# INSIDER02.net
KiCad netlist of a schematic drawn in EAGLE
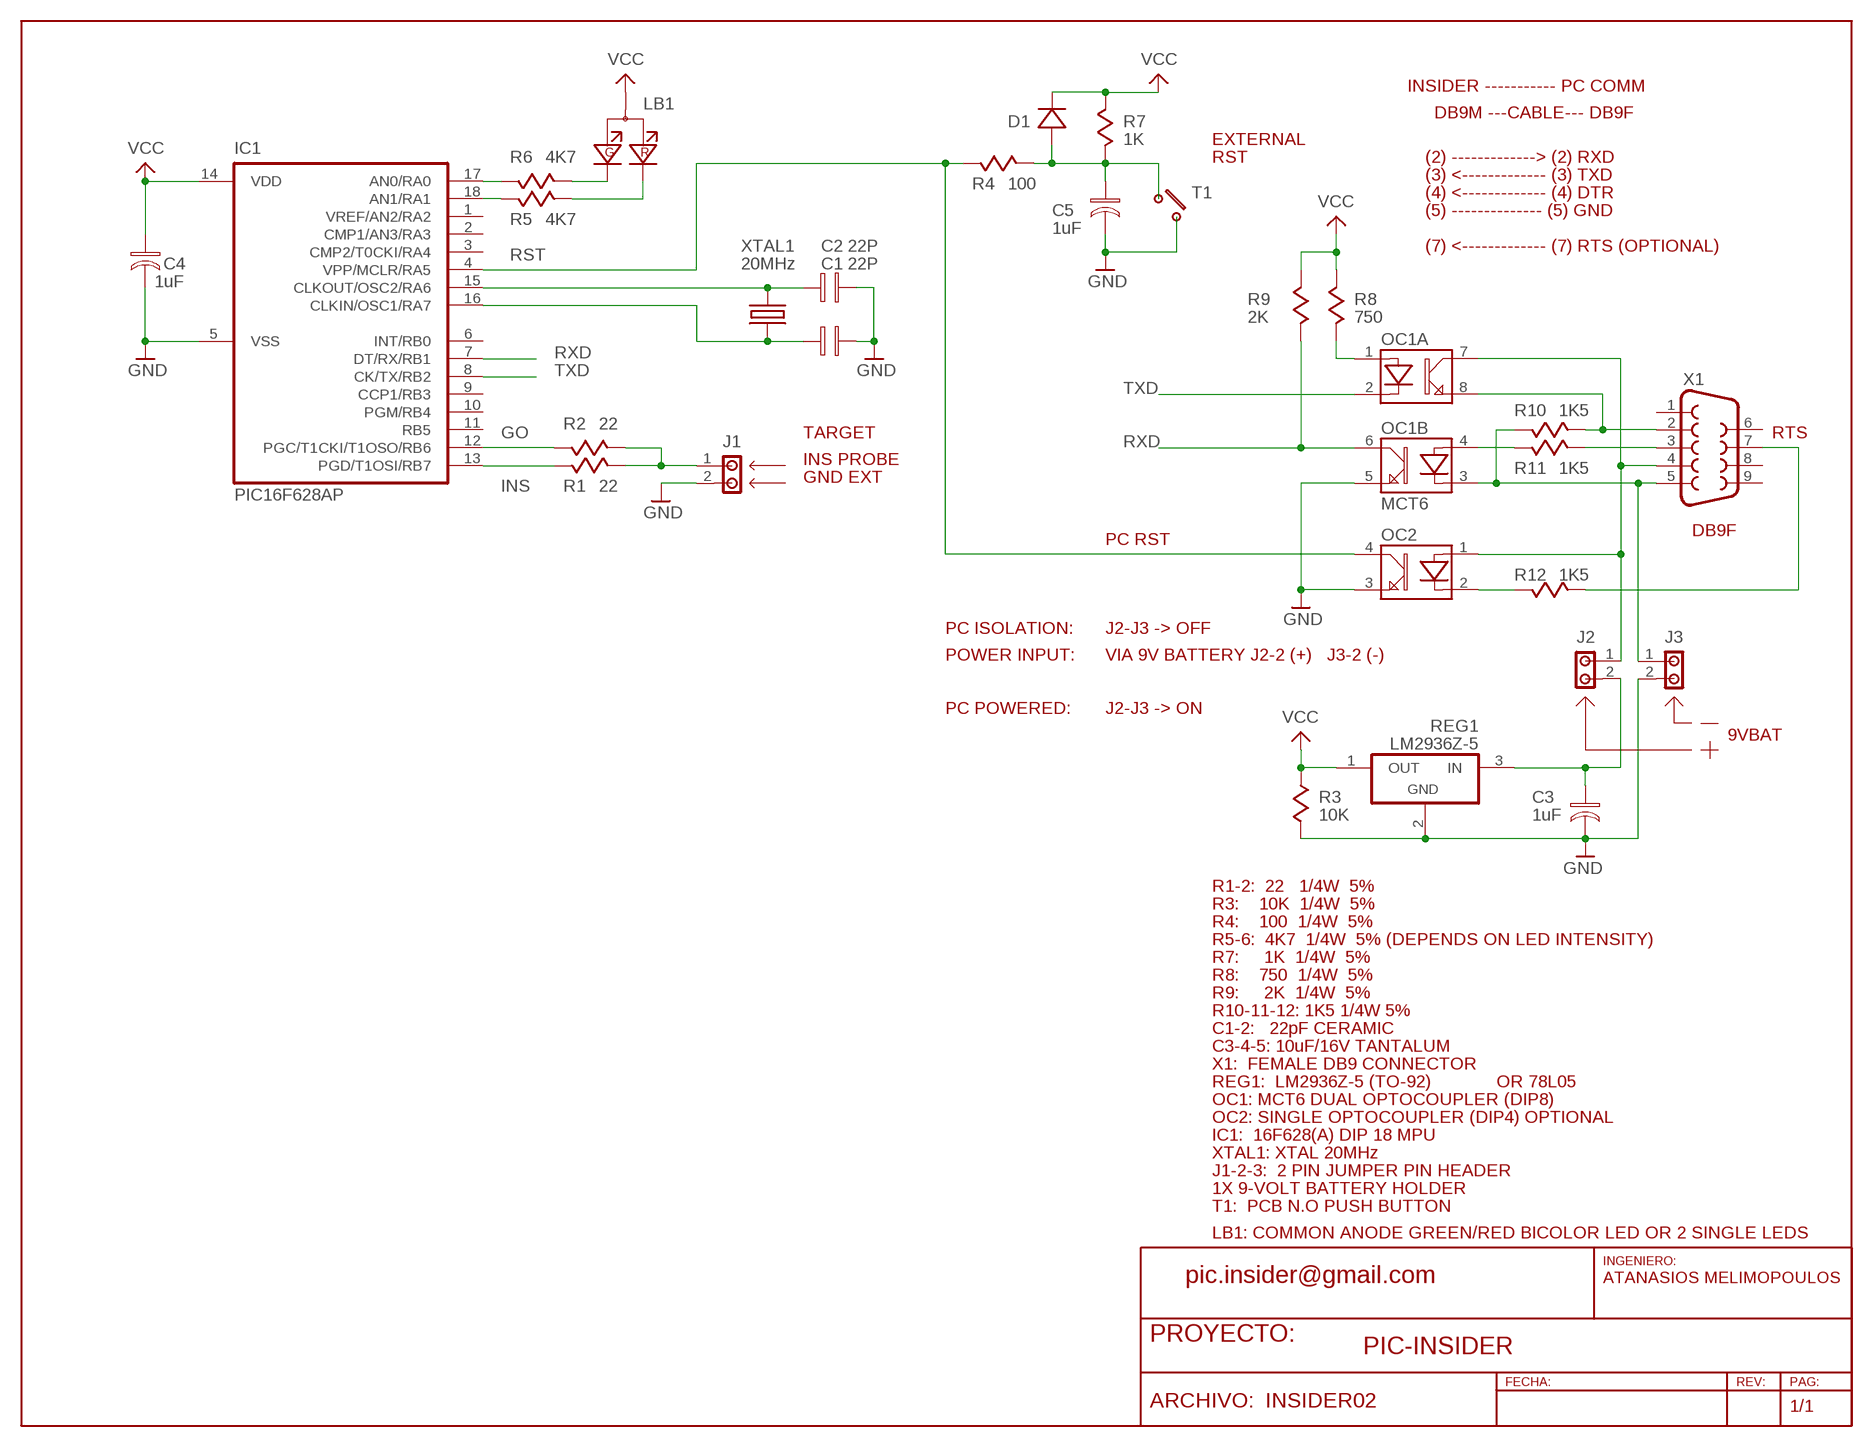
[diagram p0: schematic, sheet 1]

(export (version "E")
  (design (tool "Eeschema 10.0.6"))
  (components
    (comp (ref "C1")
      (value "22P")
      (footprint "eagle-import:C02")
      (libsource (lib "eagle-import") (part "CAP02"))
    )
    (comp (ref "C2")
      (value "22P")
      (footprint "eagle-import:C02")
      (libsource (lib "eagle-import") (part "CAP02"))
    )
    (comp (ref "C3")
      (value "1uF")
      (footprint "eagle-import:CP01")
      (libsource (lib "eagle-import") (part "CAPE01"))
    )
    (comp (ref "C4")
      (value "1uF")
      (footprint "eagle-import:CP01")
      (libsource (lib "eagle-import") (part "CAPE01"))
    )
    (comp (ref "C5")
      (value "1uF")
      (footprint "eagle-import:CP01")
      (libsource (lib "eagle-import") (part "CAPE01"))
    )
    (comp (ref "D1")
      (value "1N4148")
      (footprint "eagle-import:D03")
      (libsource (lib "eagle-import") (part "DIODE03"))
    )
    (comp (ref "IC1")
      (value "PIC16F628AP")
      (footprint "eagle-import:DIL18")
      (libsource (lib "eagle-import") (part "PIC16F6P28A"))
    )
    (comp (ref "J1")
      (value "JMP2")
      (footprint "eagle-import:JP2")
      (libsource (lib "eagle-import") (part "JMP2"))
    )
    (comp (ref "J2")
      (value "JMP2")
      (footprint "eagle-import:JP2")
      (libsource (lib "eagle-import") (part "JMP2"))
    )
    (comp (ref "J3")
      (value "JMP2")
      (footprint "eagle-import:JP2")
      (libsource (lib "eagle-import") (part "JMP2"))
    )
    (comp (ref "LB1")
      (value "LEDBIAC")
      (footprint "eagle-import:LEDBAC")
      (libsource (lib "eagle-import") (part "LEDBIAC"))
    )
    (comp (ref "OC1")
      (value "MCT6")
      (footprint "eagle-import:DIL08")
      (libsource (lib "eagle-import") (part "OPTO2G"))
    )
    (comp (ref "OC2")
      (value "OPTO1A")
      (footprint "eagle-import:DIL04")
      (libsource (lib "eagle-import") (part "OPTO1A"))
    )
    (comp (ref "R1")
      (value "22")
      (footprint "eagle-import:R03")
      (libsource (lib "eagle-import") (part "RES03"))
    )
    (comp (ref "R2")
      (value "22")
      (footprint "eagle-import:R03")
      (libsource (lib "eagle-import") (part "RES03"))
    )
    (comp (ref "R3")
      (value "10K")
      (footprint "eagle-import:R03")
      (libsource (lib "eagle-import") (part "RES03"))
    )
    (comp (ref "R4")
      (value "100")
      (footprint "eagle-import:R03")
      (libsource (lib "eagle-import") (part "RES03"))
    )
    (comp (ref "R5")
      (value "4K7")
      (footprint "eagle-import:R03")
      (libsource (lib "eagle-import") (part "RES03"))
    )
    (comp (ref "R6")
      (value "4K7")
      (footprint "eagle-import:R03")
      (libsource (lib "eagle-import") (part "RES03"))
    )
    (comp (ref "R7")
      (value "1K")
      (footprint "eagle-import:R03")
      (libsource (lib "eagle-import") (part "RES03"))
    )
    (comp (ref "R8")
      (value "750")
      (footprint "eagle-import:R03")
      (libsource (lib "eagle-import") (part "RES03"))
    )
    (comp (ref "R9")
      (value "2K")
      (footprint "eagle-import:R03")
      (libsource (lib "eagle-import") (part "RES03"))
    )
    (comp (ref "R10")
      (value "1K5")
      (footprint "eagle-import:R03")
      (libsource (lib "eagle-import") (part "RES03"))
    )
    (comp (ref "R11")
      (value "1K5")
      (footprint "eagle-import:R03")
      (libsource (lib "eagle-import") (part "RES03"))
    )
    (comp (ref "R12")
      (value "1K5")
      (footprint "eagle-import:R03")
      (libsource (lib "eagle-import") (part "RES03"))
    )
    (comp (ref "REG1")
      (value "LM2936Z-5")
      (footprint "eagle-import:TO92A")
      (libsource (lib "eagle-import") (part "78XXL"))
    )
    (comp (ref "T1")
      (value "TEC3")
      (footprint "eagle-import:TEC3L")
      (libsource (lib "eagle-import") (part "TEC3"))
    )
    (comp (ref "X1")
      (value "F09D")
      (footprint "eagle-import:F09D")
      (libsource (lib "eagle-import") (part "F09D"))
    )
    (comp (ref "XTAL1")
      (value "20MHz")
      (footprint "eagle-import:HC49V")
      (libsource (lib "eagle-import") (part "XTALV300"))
    )
  )
  (nets
    (net (code "1") (name "/GO") (class "Default")
      (node (ref "IC1") (pin "12") (pinfunction "PGC/T1CKI/T1OSO/RB6_12") (pintype "bidirectional"))
      (node (ref "R2") (pin "P$2") (pinfunction "2_P$2") (pintype "passive"))
    )
    (net (code "2") (name "/INS") (class "Default")
      (node (ref "IC1") (pin "13") (pinfunction "PGD/T1OSI/RB7_13") (pintype "bidirectional"))
      (node (ref "R1") (pin "P$1") (pinfunction "1_P$1") (pintype "passive"))
    )
    (net (code "3") (name "/RST") (class "Default")
      (node (ref "IC1") (pin "4") (pinfunction "VPP/MCLR/RA5_4") (pintype "input"))
      (node (ref "OC2") (pin "4") (pinfunction "C_4") (pintype "passive"))
      (node (ref "R4") (pin "P$2") (pinfunction "2_P$2") (pintype "passive"))
    )
    (net (code "4") (name "/RXD") (class "Default")
      (node (ref "IC1") (pin "7") (pinfunction "DT/RX/RB1_7") (pintype "bidirectional"))
      (node (ref "OC1") (pin "6") (pinfunction "C_6") (pintype "passive"))
      (node (ref "R9") (pin "P$2") (pinfunction "2_P$2") (pintype "passive"))
    )
    (net (code "5") (name "/TXD") (class "Default")
      (node (ref "IC1") (pin "8") (pinfunction "CK/TX/RB2_8") (pintype "bidirectional"))
      (node (ref "OC1") (pin "2") (pinfunction "K_2") (pintype "passive"))
    )
    (net (code "6") (name "GND") (class "Default")
      (node (ref "C1") (pin "P$2") (pinfunction "2_P$2") (pintype "passive"))
      (node (ref "C2") (pin "P$2") (pinfunction "2_P$2") (pintype "passive"))
      (node (ref "C3") (pin "P$2") (pinfunction "2_P$2") (pintype "passive"))
      (node (ref "C4") (pin "P$2") (pinfunction "2_P$2") (pintype "passive"))
      (node (ref "C5") (pin "P$2") (pinfunction "2_P$2") (pintype "passive"))
      (node (ref "IC1") (pin "5") (pinfunction "VSS_5") (pintype "power_in"))
      (node (ref "J1") (pin "2") (pinfunction "P$2_2") (pintype "bidirectional"))
      (node (ref "J3") (pin "2") (pinfunction "P$2_2") (pintype "bidirectional"))
      (node (ref "OC1") (pin "5") (pinfunction "E_5") (pintype "passive"))
      (node (ref "OC2") (pin "3") (pinfunction "E_3") (pintype "passive"))
      (node (ref "R3") (pin "P$2") (pinfunction "2_P$2") (pintype "passive"))
      (node (ref "REG1") (pin "2") (pinfunction "GND_2") (pintype "input"))
      (node (ref "T1") (pin "1") (pinfunction "P$1_1") (pintype "passive"))
    )
    (net (code "7") (name "Net-(C1-1)") (class "Default")
      (node (ref "C1") (pin "P$1") (pinfunction "1_P$1") (pintype "passive"))
      (node (ref "IC1") (pin "16") (pinfunction "CLKIN/OSC1/RA7_16") (pintype "bidirectional"))
      (node (ref "XTAL1") (pin "2") (pinfunction "P$2_2") (pintype "passive"))
    )
    (net (code "8") (name "Net-(C2-1)") (class "Default")
      (node (ref "C2") (pin "P$1") (pinfunction "1_P$1") (pintype "passive"))
      (node (ref "IC1") (pin "15") (pinfunction "CLKOUT/OSC2/RA6_15") (pintype "bidirectional"))
      (node (ref "XTAL1") (pin "1") (pinfunction "P$1_1") (pintype "passive"))
    )
    (net (code "9") (name "Net-(C3-1)") (class "Default")
      (node (ref "C3") (pin "P$1") (pinfunction "1_P$1") (pintype "passive"))
      (node (ref "J2") (pin "2") (pinfunction "P$2_2") (pintype "bidirectional"))
      (node (ref "REG1") (pin "3") (pinfunction "IN_3") (pintype "input"))
    )
    (net (code "10") (name "Net-(C5-1)") (class "Default")
      (node (ref "C5") (pin "P$1") (pinfunction "1_P$1") (pintype "passive"))
      (node (ref "D1") (pin "P$1") (pinfunction "A_P$1") (pintype "passive"))
      (node (ref "R4") (pin "P$1") (pinfunction "1_P$1") (pintype "passive"))
      (node (ref "R7") (pin "P$2") (pinfunction "2_P$2") (pintype "passive"))
      (node (ref "T1") (pin "4") (pinfunction "P$2_4") (pintype "passive"))
    )
    (net (code "11") (name "Net-(IC1-AN0{slash}RA0)") (class "Default")
      (node (ref "IC1") (pin "17") (pinfunction "AN0/RA0_17") (pintype "bidirectional"))
      (node (ref "R6") (pin "P$2") (pinfunction "2_P$2") (pintype "passive"))
    )
    (net (code "12") (name "Net-(IC1-AN1{slash}RA1)") (class "Default")
      (node (ref "IC1") (pin "18") (pinfunction "AN1/RA1_18") (pintype "bidirectional"))
      (node (ref "R5") (pin "P$2") (pinfunction "2_P$2") (pintype "passive"))
    )
    (net (code "13") (name "Net-(J1-P$1)") (class "Default")
      (node (ref "J1") (pin "1") (pinfunction "P$1_1") (pintype "bidirectional"))
      (node (ref "R1") (pin "P$2") (pinfunction "2_P$2") (pintype "passive"))
      (node (ref "R2") (pin "P$1") (pinfunction "1_P$1") (pintype "passive"))
    )
    (net (code "14") (name "Net-(J2-P$1)") (class "Default")
      (node (ref "J2") (pin "1") (pinfunction "P$1_1") (pintype "bidirectional"))
      (node (ref "OC1") (pin "7") (pinfunction "C_7") (pintype "passive"))
      (node (ref "OC2") (pin "1") (pinfunction "A_1") (pintype "passive"))
      (node (ref "X1") (pin "4") (pinfunction "4_4") (pintype "passive"))
    )
    (net (code "15") (name "Net-(J3-P$1)") (class "Default")
      (node (ref "J3") (pin "1") (pinfunction "P$1_1") (pintype "bidirectional"))
      (node (ref "OC1") (pin "3") (pinfunction "K_3") (pintype "passive"))
      (node (ref "R10") (pin "P$1") (pinfunction "1_P$1") (pintype "passive"))
      (node (ref "X1") (pin "5") (pinfunction "5_5") (pintype "passive"))
    )
    (net (code "16") (name "Net-(LB1-K1)") (class "Default")
      (node (ref "LB1") (pin "R") (pinfunction "K1_R") (pintype "passive"))
      (node (ref "R5") (pin "P$1") (pinfunction "1_P$1") (pintype "passive"))
    )
    (net (code "17") (name "Net-(LB1-K2)") (class "Default")
      (node (ref "LB1") (pin "G") (pinfunction "K2_G") (pintype "passive"))
      (node (ref "R6") (pin "P$1") (pinfunction "1_P$1") (pintype "passive"))
    )
    (net (code "18") (name "Net-(OC1A-A)") (class "Default")
      (node (ref "OC1") (pin "1") (pinfunction "A_1") (pintype "passive"))
      (node (ref "R8") (pin "P$2") (pinfunction "2_P$2") (pintype "passive"))
    )
    (net (code "19") (name "Net-(OC1A-E)") (class "Default")
      (node (ref "OC1") (pin "8") (pinfunction "E_8") (pintype "passive"))
      (node (ref "R10") (pin "P$2") (pinfunction "2_P$2") (pintype "passive"))
      (node (ref "X1") (pin "2") (pinfunction "2_2") (pintype "passive"))
    )
    (net (code "20") (name "Net-(OC1B-A)") (class "Default")
      (node (ref "OC1") (pin "4") (pinfunction "A_4") (pintype "passive"))
      (node (ref "R11") (pin "P$1") (pinfunction "1_P$1") (pintype "passive"))
    )
    (net (code "21") (name "Net-(OC2-K)") (class "Default")
      (node (ref "OC2") (pin "2") (pinfunction "K_2") (pintype "passive"))
      (node (ref "R12") (pin "P$1") (pinfunction "1_P$1") (pintype "passive"))
    )
    (net (code "22") (name "Net-(R11-2)") (class "Default")
      (node (ref "R11") (pin "P$2") (pinfunction "2_P$2") (pintype "passive"))
      (node (ref "X1") (pin "3") (pinfunction "3_3") (pintype "passive"))
    )
    (net (code "23") (name "Net-(R12-2)") (class "Default")
      (node (ref "R12") (pin "P$2") (pinfunction "2_P$2") (pintype "passive"))
      (node (ref "X1") (pin "7") (pinfunction "7_7") (pintype "passive"))
    )
    (net (code "24") (name "VCC") (class "Default")
      (node (ref "C4") (pin "P$1") (pinfunction "1_P$1") (pintype "passive"))
      (node (ref "D1") (pin "P$2") (pinfunction "K_P$2") (pintype "passive"))
      (node (ref "IC1") (pin "14") (pinfunction "VDD_14") (pintype "power_in"))
      (node (ref "LB1") (pin "A") (pinfunction "A_A") (pintype "passive"))
      (node (ref "R3") (pin "P$1") (pinfunction "1_P$1") (pintype "passive"))
      (node (ref "R7") (pin "P$1") (pinfunction "1_P$1") (pintype "passive"))
      (node (ref "R8") (pin "P$1") (pinfunction "1_P$1") (pintype "passive"))
      (node (ref "R9") (pin "P$1") (pinfunction "1_P$1") (pintype "passive"))
      (node (ref "REG1") (pin "1") (pinfunction "OUT_1") (pintype "passive"))
    )
    (net (code "25") (name "unconnected-(IC1-CCP1{slash}RB3-Pad9)") (class "Default")
      (node (ref "IC1") (pin "9") (pinfunction "CCP1/RB3_9") (pintype "bidirectional"))
    )
    (net (code "26") (name "unconnected-(IC1-CMP1{slash}AN3{slash}RA3-Pad2)") (class "Default")
      (node (ref "IC1") (pin "2") (pinfunction "CMP1/AN3/RA3_2") (pintype "bidirectional"))
    )
    (net (code "27") (name "unconnected-(IC1-CMP2{slash}T0CKI{slash}RA4-Pad3)") (class "Default")
      (node (ref "IC1") (pin "3") (pinfunction "CMP2/T0CKI/RA4_3") (pintype "bidirectional"))
    )
    (net (code "28") (name "unconnected-(IC1-INT{slash}RB0-Pad6)") (class "Default")
      (node (ref "IC1") (pin "6") (pinfunction "INT/RB0_6") (pintype "bidirectional"))
    )
    (net (code "29") (name "unconnected-(IC1-PGM{slash}RB4-Pad10)") (class "Default")
      (node (ref "IC1") (pin "10") (pinfunction "PGM/RB4_10") (pintype "bidirectional"))
    )
    (net (code "30") (name "unconnected-(IC1-RB5-Pad11)") (class "Default")
      (node (ref "IC1") (pin "11") (pinfunction "RB5_11") (pintype "bidirectional"))
    )
    (net (code "31") (name "unconnected-(IC1-VREF{slash}AN2{slash}RA2-Pad1)") (class "Default")
      (node (ref "IC1") (pin "1") (pinfunction "VREF/AN2/RA2_1") (pintype "bidirectional"))
    )
    (net (code "32") (name "unconnected-(X1-Pad1)") (class "Default")
      (node (ref "X1") (pin "1") (pinfunction "1_1") (pintype "passive"))
    )
    (net (code "33") (name "unconnected-(X1-Pad6)") (class "Default")
      (node (ref "X1") (pin "6") (pinfunction "6_6") (pintype "passive"))
    )
    (net (code "34") (name "unconnected-(X1-Pad8)") (class "Default")
      (node (ref "X1") (pin "8") (pinfunction "8_8") (pintype "passive"))
    )
    (net (code "35") (name "unconnected-(X1-Pad9)") (class "Default")
      (node (ref "X1") (pin "9") (pinfunction "9_9") (pintype "passive"))
    )
  )
)
